# Voltage_detectV2.net
KiCad netlist of a schematic drawn in Altium Designer
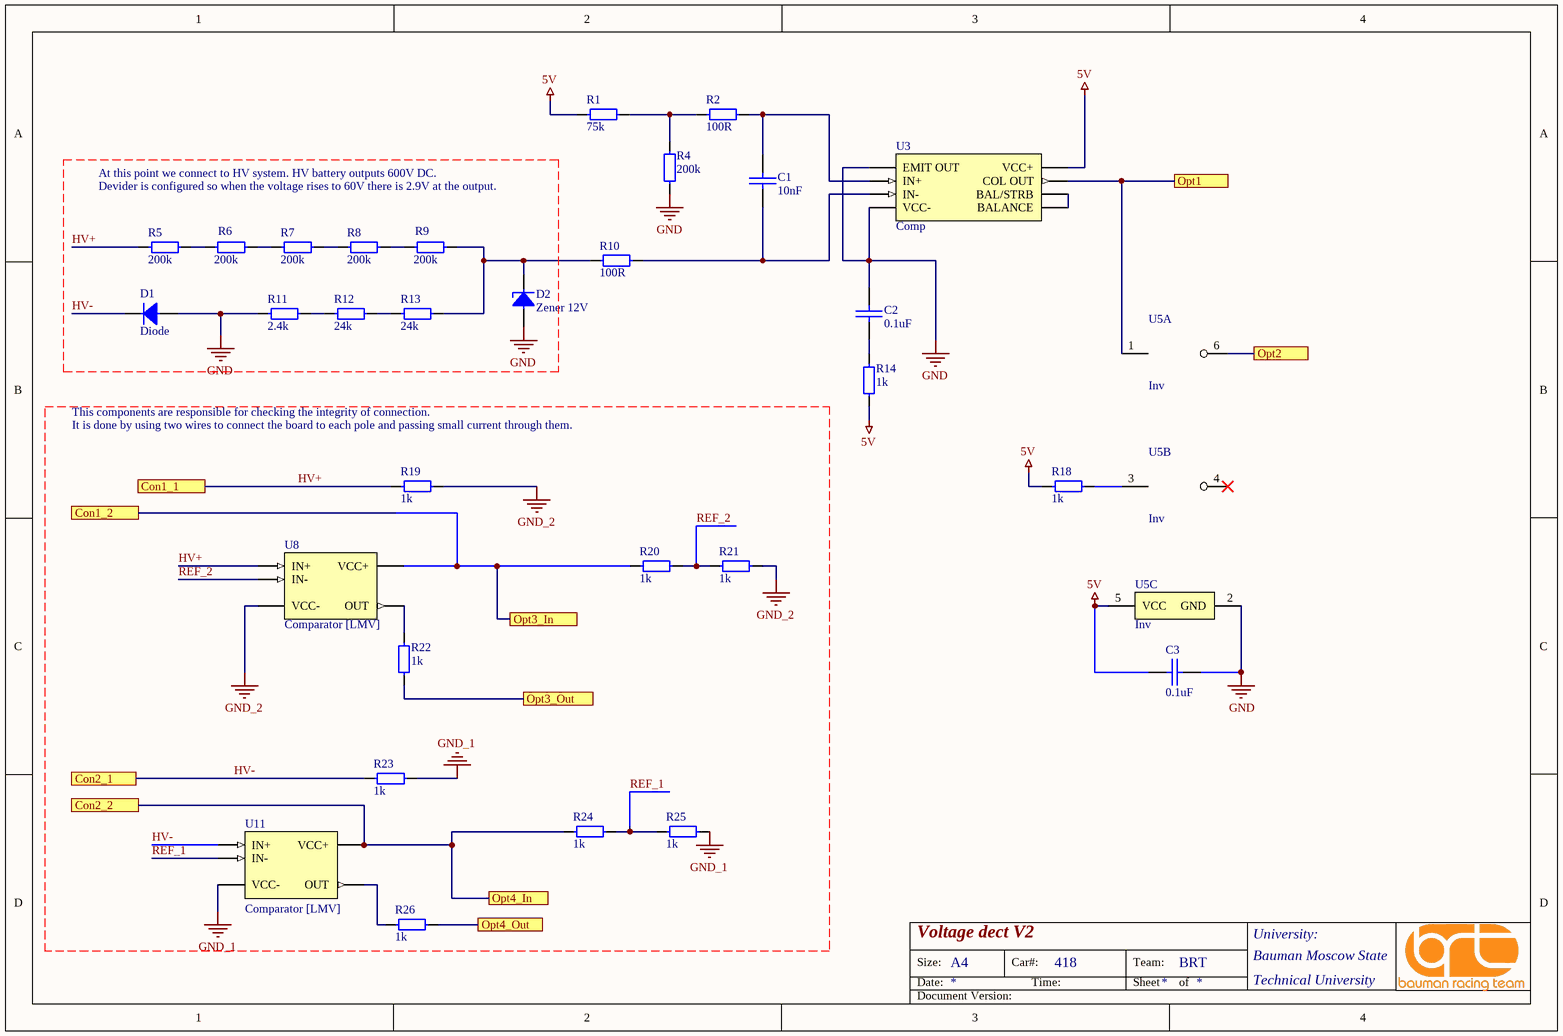
[diagram p0: Voltage detectV2.SchDoc]

(export (version "E")
  (design (tool "Eeschema 10.0.6"))
  (components
    (comp (ref "C1")
      (value "10nF")
      (footprint "0805 Capicator")
      (description "0805 X7R 10nF 100V 10%")
      (fields
        (field (name "MANUFACTURER") "Murata Manufacturing")
        (field (name "PART NUMBER") "GRM21BR72A103KA01L")
      )
      (libsource (lib "BRT_Components") (part "Cap 10nF (0805)"))
    )
    (comp (ref "C2")
      (value "0.1uF")
      (footprint "0805 Capicator")
      (description "0.1uF X7R 25V 10% 0805")
      (fields
        (field (name "MANUFACTURER") "Murata Manufacturing")
        (field (name "PART NUMBER") "GRM21BR71E104KA01L")
      )
      (libsource (lib "BRT_Components") (part "Cap 0.1uF (0805)"))
    )
    (comp (ref "C3")
      (value "0.1uF")
      (footprint "0805 Capicator")
      (description "0.1uF X7R 25V 10% 0805")
      (fields
        (field (name "MANUFACTURER") "Murata Manufacturing")
        (field (name "PART NUMBER") "GRM21BR71E104KA01L")
      )
      (libsource (lib "BRT_Components") (part "Cap 0.1uF (0805)"))
    )
    (comp (ref "D1")
      (value "Diode")
      (footprint "DO-41")
      (description "Highg voltage diode - 2000V")
      (fields (field (name "PART NUMBER") "EM518") (field (name "MANUFACTURER") "China"))
      (libsource (lib "BRT_Components") (part "Diode HV [EM5]"))
    )
    (comp (ref "D2")
      (value "Zener 12V")
      (footprint "sod-323")
      (description "300mW")
      (fields (field (name "PART NUMBER") "BZX384-C12,115") (field (name "MANUFACTURER") "NXP Semiconductor"))
      (libsource (lib "BRT_Components") (part "Zener Diode 12V"))
    )
    (comp (ref "R1")
      (value "75k")
      (footprint "0805 Resistor")
      (description "0.125W 0805 75k, 1%")
      (fields (field (name "PART NUMBER") "RC0805FR-0775KL") (field (name "MANUFACTURER") "Taiwan"))
      (libsource (lib "BRT_Components") (part "Res 75k (0805)"))
    )
    (comp (ref "R2")
      (value "100R")
      (footprint "0805 Resistor")
      (description "0.125W 0805 100R, 1%")
      (fields (field (name "PART NUMBER") "RC0805FR-07100RL") (field (name "MANUFACTURER") "Taiwan"))
      (libsource (lib "BRT_Components") (part "Res 100R (0805)"))
    )
    (comp (ref "R4")
      (value "200k")
      (footprint "0805 Resistor")
      (description "0.125W 0805 200k, 1%")
      (fields (field (name "PART NUMBER") "RC0805FK-07200KL") (field (name "MANUFACTURER") "Taiwan"))
      (libsource (lib "BRT_Components") (part "Res 200k (0805)"))
    )
    (comp (ref "R5")
      (value "200k")
      (footprint "0805 Resistor")
      (description "0.125W 0805 200k, 1%")
      (fields (field (name "PART NUMBER") "RC0805FK-07200KL") (field (name "MANUFACTURER") "Taiwan"))
      (libsource (lib "BRT_Components") (part "Res 200k (0805)"))
    )
    (comp (ref "R6")
      (value "200k")
      (footprint "0805 Resistor")
      (description "0.125W 0805 200k, 1%")
      (fields (field (name "PART NUMBER") "RC0805FK-07200KL") (field (name "MANUFACTURER") "Taiwan"))
      (libsource (lib "BRT_Components") (part "Res 200k (0805)"))
    )
    (comp (ref "R7")
      (value "200k")
      (footprint "0805 Resistor")
      (description "0.125W 0805 200k, 1%")
      (fields (field (name "PART NUMBER") "RC0805FK-07200KL") (field (name "MANUFACTURER") "Taiwan"))
      (libsource (lib "BRT_Components") (part "Res 200k (0805)"))
    )
    (comp (ref "R8")
      (value "200k")
      (footprint "0805 Resistor")
      (description "0.125W 0805 200k, 1%")
      (fields (field (name "PART NUMBER") "RC0805FK-07200KL") (field (name "MANUFACTURER") "Taiwan"))
      (libsource (lib "BRT_Components") (part "Res 200k (0805)"))
    )
    (comp (ref "R9")
      (value "200k")
      (footprint "0805 Resistor")
      (description "0.125W 0805 200k, 1%")
      (fields (field (name "PART NUMBER") "RC0805FK-07200KL") (field (name "MANUFACTURER") "Taiwan"))
      (libsource (lib "BRT_Components") (part "Res 200k (0805)"))
    )
    (comp (ref "R10")
      (value "100R")
      (footprint "0805 Resistor")
      (description "0.125W 0805 100R, 1%")
      (fields (field (name "PART NUMBER") "RC0805FR-07100RL") (field (name "MANUFACTURER") "Taiwan"))
      (libsource (lib "BRT_Components") (part "Res 100R (0805)"))
    )
    (comp (ref "R11")
      (value "2.4k")
      (footprint "0805 Resistor")
      (description "0.125W 0805 2.4k, 1%")
      (fields (field (name "PART NUMBER") "RC0805FR-072K4L") (field (name "MANUFACTURER") "Taiwan"))
      (libsource (lib "BRT_Components") (part "Res 2.4k (0805)"))
    )
    (comp (ref "R12")
      (value "24k")
      (footprint "0805 Resistor")
      (description "0.125W 0805 24k, 1%")
      (fields (field (name "PART NUMBER") "RC0805FR-0724KL") (field (name "MANUFACTURER") "Taiwan"))
      (libsource (lib "BRT_Components") (part "Res 24k (0805)"))
    )
    (comp (ref "R13")
      (value "24k")
      (footprint "0805 Resistor")
      (description "0.125W 0805 24k, 1%")
      (fields (field (name "PART NUMBER") "RC0805FR-0724KL") (field (name "MANUFACTURER") "Taiwan"))
      (libsource (lib "BRT_Components") (part "Res 24k (0805)"))
    )
    (comp (ref "R14")
      (value "1k")
      (footprint "0805 Resistor")
      (description "0.125W 0805 1k, 1%")
      (fields (field (name "PART NUMBER") "RC0805FR-071KL") (field (name "MANUFACTURER") "Taiwan"))
      (libsource (lib "BRT_Components") (part "Res 1k (0805)"))
    )
    (comp (ref "R18")
      (value "1k")
      (footprint "0805 Resistor")
      (description "0.125W 0805 1k, 1%")
      (fields (field (name "PART NUMBER") "RC0805FR-071KL") (field (name "MANUFACTURER") "Taiwan"))
      (libsource (lib "BRT_Components") (part "Res 1k (0805)"))
    )
    (comp (ref "R19")
      (value "1k")
      (footprint "0805 Resistor")
      (description "0.125W 0805 1k, 1%")
      (fields (field (name "PART NUMBER") "RC0805FR-071KL") (field (name "MANUFACTURER") "Taiwan"))
      (libsource (lib "BRT_Components") (part "Res 1k (0805)"))
    )
    (comp (ref "R20")
      (value "1k")
      (footprint "0805 Resistor")
      (description "0.125W 0805 1k, 1%")
      (fields (field (name "PART NUMBER") "RC0805FR-071KL") (field (name "MANUFACTURER") "Taiwan"))
      (libsource (lib "BRT_Components") (part "Res 1k (0805)"))
    )
    (comp (ref "R21")
      (value "1k")
      (footprint "0805 Resistor")
      (description "0.125W 0805 1k, 1%")
      (fields (field (name "PART NUMBER") "RC0805FR-071KL") (field (name "MANUFACTURER") "Taiwan"))
      (libsource (lib "BRT_Components") (part "Res 1k (0805)"))
    )
    (comp (ref "R22")
      (value "1k")
      (footprint "0805 Resistor")
      (description "0.125W 0805 1k, 1%")
      (fields (field (name "PART NUMBER") "RC0805FR-071KL") (field (name "MANUFACTURER") "Taiwan"))
      (libsource (lib "BRT_Components") (part "Res 1k (0805)"))
    )
    (comp (ref "R23")
      (value "1k")
      (footprint "0805 Resistor")
      (description "0.125W 0805 1k, 1%")
      (fields (field (name "PART NUMBER") "RC0805FR-071KL") (field (name "MANUFACTURER") "Taiwan"))
      (libsource (lib "BRT_Components") (part "Res 1k (0805)"))
    )
    (comp (ref "R24")
      (value "1k")
      (footprint "0805 Resistor")
      (description "0.125W 0805 1k, 1%")
      (fields (field (name "PART NUMBER") "RC0805FR-071KL") (field (name "MANUFACTURER") "Taiwan"))
      (libsource (lib "BRT_Components") (part "Res 1k (0805)"))
    )
    (comp (ref "R25")
      (value "1k")
      (footprint "0805 Resistor")
      (description "0.125W 0805 1k, 1%")
      (fields (field (name "PART NUMBER") "RC0805FR-071KL") (field (name "MANUFACTURER") "Taiwan"))
      (libsource (lib "BRT_Components") (part "Res 1k (0805)"))
    )
    (comp (ref "R26")
      (value "1k")
      (footprint "0805 Resistor")
      (description "0.125W 0805 1k, 1%")
      (fields (field (name "PART NUMBER") "RC0805FR-071KL") (field (name "MANUFACTURER") "Taiwan"))
      (libsource (lib "BRT_Components") (part "Res 1k (0805)"))
    )
    (comp (ref "U3")
      (value "Comp")
      (footprint "SOIC-8")
      (description "Differential comparator with strobes")
      (fields (field (name "PART NUMBER") "LM311DR") (field (name "MANUFACTURER") "Texas Instruments"))
      (libsource (lib "BRT_Components") (part "Comparator [LM3]"))
    )
    (comp (ref "U5")
      (value "Inv")
      (footprint "SOT236")
      (description "Dual inverter, 1.65-5.5V")
      (fields
        (field (name "MANUFACTURER") "Texas Instruments")
        (field (name "PART NUMBER") "SN74LVC2G04DBVR")
      )
      (libsource (lib "BRT_Components") (part "Inverter (SN74)"))
    )
    (comp (ref "U8")
      (value "Comparator [LMV]")
      (footprint "SOT-23-5")
      (description "Differential comparator with strobes")
      (fields (field (name "PART NUMBER") "LMV331M5/NOPB") (field (name "MANUFACTURER") "Texas Instruments"))
      (libsource (lib "BRT_Components") (part "Comparator [LMV]"))
    )
    (comp (ref "U11")
      (value "Comparator [LMV]")
      (footprint "SOT-23-5")
      (description "Differential comparator with strobes")
      (fields (field (name "PART NUMBER") "LMV331M5/NOPB") (field (name "MANUFACTURER") "Texas Instruments"))
      (libsource (lib "BRT_Components") (part "Comparator [LMV]"))
    )
  )
  (nets
    (net (code "1") (name "/Con1_2") (class "Default")
      (node (ref "R20") (pin "2") (pinfunction "2_2") (pintype "passive"))
      (node (ref "U8") (pin "5") (pinfunction "VCC+_5") (pintype "power_in"))
    )
    (net (code "2") (name "/Con2_2") (class "Default")
      (node (ref "R24") (pin "2") (pinfunction "2_2") (pintype "passive"))
      (node (ref "U11") (pin "5") (pinfunction "VCC+_5") (pintype "power_in"))
    )
    (net (code "3") (name "/HV+") (class "Default")
      (node (ref "R19") (pin "2") (pinfunction "2_2") (pintype "passive"))
      (node (ref "R5") (pin "1") (pinfunction "1_1") (pintype "passive"))
      (node (ref "U8") (pin "1") (pinfunction "IN+_1") (pintype "input"))
    )
    (net (code "4") (name "/HV-") (class "Default")
      (node (ref "D1") (pin "2") (pinfunction "2_2") (pintype "passive"))
      (node (ref "R23") (pin "2") (pinfunction "2_2") (pintype "passive"))
      (node (ref "U11") (pin "1") (pinfunction "IN+_1") (pintype "input"))
    )
    (net (code "5") (name "/Opt1") (class "Default")
      (node (ref "U3") (pin "7") (pinfunction "COL_OUT_7") (pintype "output"))
      (node (ref "U5") (pin "1") (pinfunction "1A_1") (pintype "passive"))
    )
    (net (code "6") (name "/Opt2") (class "Default")
      (node (ref "U5") (pin "6") (pinfunction "1Y_6") (pintype "passive"))
    )
    (net (code "7") (name "/Opt3_Out") (class "Default")
      (node (ref "R22") (pin "2") (pinfunction "2_2") (pintype "passive"))
    )
    (net (code "8") (name "/Opt4_Out") (class "Default")
      (node (ref "R26") (pin "2") (pinfunction "2_2") (pintype "passive"))
    )
    (net (code "9") (name "/REF_1") (class "Default")
      (node (ref "R24") (pin "1") (pinfunction "1_1") (pintype "passive"))
      (node (ref "R25") (pin "2") (pinfunction "2_2") (pintype "passive"))
      (node (ref "U11") (pin "3") (pinfunction "IN-_3") (pintype "input"))
    )
    (net (code "10") (name "/REF_2") (class "Default")
      (node (ref "R20") (pin "1") (pinfunction "1_1") (pintype "passive"))
      (node (ref "R21") (pin "2") (pinfunction "2_2") (pintype "passive"))
      (node (ref "U8") (pin "3") (pinfunction "IN-_3") (pintype "input"))
    )
    (net (code "11") (name "5V") (class "Default")
      (node (ref "C3") (pin "1") (pinfunction "1_1") (pintype "passive"))
      (node (ref "R1") (pin "1") (pinfunction "1_1") (pintype "passive"))
      (node (ref "R14") (pin "1") (pinfunction "1_1") (pintype "passive"))
      (node (ref "R18") (pin "2") (pinfunction "2_2") (pintype "passive"))
      (node (ref "U3") (pin "8") (pinfunction "VCC+_8") (pintype "power_in"))
      (node (ref "U5") (pin "5") (pinfunction "VCC_5") (pintype "power_in"))
    )
    (net (code "12") (name "GND") (class "Default")
      (node (ref "C2") (pin "2") (pinfunction "2_2") (pintype "passive"))
      (node (ref "C3") (pin "2") (pinfunction "2_2") (pintype "passive"))
      (node (ref "D1") (pin "1") (pinfunction "1_1") (pintype "passive"))
      (node (ref "D2") (pin "1") (pinfunction "1_1") (pintype "passive"))
      (node (ref "R11") (pin "1") (pinfunction "1_1") (pintype "passive"))
      (node (ref "R4") (pin "1") (pinfunction "1_1") (pintype "passive"))
      (node (ref "U3") (pin "1") (pinfunction "EMIT_OUT_1") (pintype "passive"))
      (node (ref "U3") (pin "4") (pinfunction "VCC-_4") (pintype "power_in"))
      (node (ref "U5") (pin "2") (pinfunction "GND_2") (pintype "power_in"))
    )
    (net (code "13") (name "GND_1") (class "Default")
      (node (ref "R23") (pin "1") (pinfunction "1_1") (pintype "passive"))
      (node (ref "R25") (pin "1") (pinfunction "1_1") (pintype "passive"))
      (node (ref "U11") (pin "2") (pinfunction "VCC-_2") (pintype "power_in"))
    )
    (net (code "14") (name "GND_2") (class "Default")
      (node (ref "R19") (pin "1") (pinfunction "1_1") (pintype "passive"))
      (node (ref "R21") (pin "1") (pinfunction "1_1") (pintype "passive"))
      (node (ref "U8") (pin "2") (pinfunction "VCC-_2") (pintype "power_in"))
    )
    (net (code "15") (name "Net-(C2-Pad1)") (class "Default")
      (node (ref "C2") (pin "1") (pinfunction "1_1") (pintype "passive"))
      (node (ref "R14") (pin "2") (pinfunction "2_2") (pintype "passive"))
    )
    (net (code "16") (name "Net-(D2-Pad2)") (class "Default")
      (node (ref "D2") (pin "2") (pinfunction "2_2") (pintype "passive"))
      (node (ref "R10") (pin "1") (pinfunction "1_1") (pintype "passive"))
      (node (ref "R13") (pin "2") (pinfunction "2_2") (pintype "passive"))
      (node (ref "R9") (pin "2") (pinfunction "2_2") (pintype "passive"))
    )
    (net (code "17") (name "Net-(R1-Pad2)") (class "Default")
      (node (ref "R1") (pin "2") (pinfunction "2_2") (pintype "passive"))
      (node (ref "R2") (pin "1") (pinfunction "1_1") (pintype "passive"))
      (node (ref "R4") (pin "2") (pinfunction "2_2") (pintype "passive"))
    )
    (net (code "18") (name "Net-(R5-Pad2)") (class "Default")
      (node (ref "R5") (pin "2") (pinfunction "2_2") (pintype "passive"))
      (node (ref "R6") (pin "1") (pinfunction "1_1") (pintype "passive"))
    )
    (net (code "19") (name "Net-(R6-Pad2)") (class "Default")
      (node (ref "R6") (pin "2") (pinfunction "2_2") (pintype "passive"))
      (node (ref "R7") (pin "1") (pinfunction "1_1") (pintype "passive"))
    )
    (net (code "20") (name "Net-(R7-Pad2)") (class "Default")
      (node (ref "R7") (pin "2") (pinfunction "2_2") (pintype "passive"))
      (node (ref "R8") (pin "1") (pinfunction "1_1") (pintype "passive"))
    )
    (net (code "21") (name "Net-(R8-Pad2)") (class "Default")
      (node (ref "R8") (pin "2") (pinfunction "2_2") (pintype "passive"))
      (node (ref "R9") (pin "1") (pinfunction "1_1") (pintype "passive"))
    )
    (net (code "22") (name "Net-(R11-Pad2)") (class "Default")
      (node (ref "R11") (pin "2") (pinfunction "2_2") (pintype "passive"))
      (node (ref "R12") (pin "2") (pinfunction "2_2") (pintype "passive"))
    )
    (net (code "23") (name "Net-(R12-Pad1)") (class "Default")
      (node (ref "R12") (pin "1") (pinfunction "1_1") (pintype "passive"))
      (node (ref "R13") (pin "1") (pinfunction "1_1") (pintype "passive"))
    )
    (net (code "24") (name "Net-(U3-BALANCE)") (class "Default")
      (node (ref "U3") (pin "5") (pinfunction "BALANCE_5") (pintype "open_collector"))
      (node (ref "U3") (pin "6") (pinfunction "BAL/STRB_6") (pintype "open_collector"))
    )
    (net (code "25") (name "Net-(U3-IN+)") (class "Default")
      (node (ref "C1") (pin "2") (pinfunction "2_2") (pintype "passive"))
      (node (ref "R2") (pin "2") (pinfunction "2_2") (pintype "passive"))
      (node (ref "U3") (pin "2") (pinfunction "IN+_2") (pintype "input"))
    )
    (net (code "26") (name "Net-(U3-IN-)") (class "Default")
      (node (ref "C1") (pin "1") (pinfunction "1_1") (pintype "passive"))
      (node (ref "R10") (pin "2") (pinfunction "2_2") (pintype "passive"))
      (node (ref "U3") (pin "3") (pinfunction "IN-_3") (pintype "input"))
    )
    (net (code "27") (name "Net-(U5B-2А)") (class "Default")
      (node (ref "R18") (pin "1") (pinfunction "1_1") (pintype "passive"))
      (node (ref "U5") (pin "3") (pinfunction "2А_3") (pintype "passive"))
    )
    (net (code "28") (name "Net-(U8-OUT)") (class "Default")
      (node (ref "R22") (pin "1") (pinfunction "1_1") (pintype "passive"))
      (node (ref "U8") (pin "4") (pinfunction "OUT_4") (pintype "output"))
    )
    (net (code "29") (name "Net-(U11-OUT)") (class "Default")
      (node (ref "R26") (pin "1") (pinfunction "1_1") (pintype "passive"))
      (node (ref "U11") (pin "4") (pinfunction "OUT_4") (pintype "output"))
    )
    (net (code "30") (name "unconnected-(U5B-2Y-Pad4)") (class "Default")
      (node (ref "U5") (pin "4") (pinfunction "2Y_4") (pintype "passive+no_connect"))
    )
  )
)
